# ST-LinkV2.net
KiCad netlist of a schematic drawn in Altium Designer
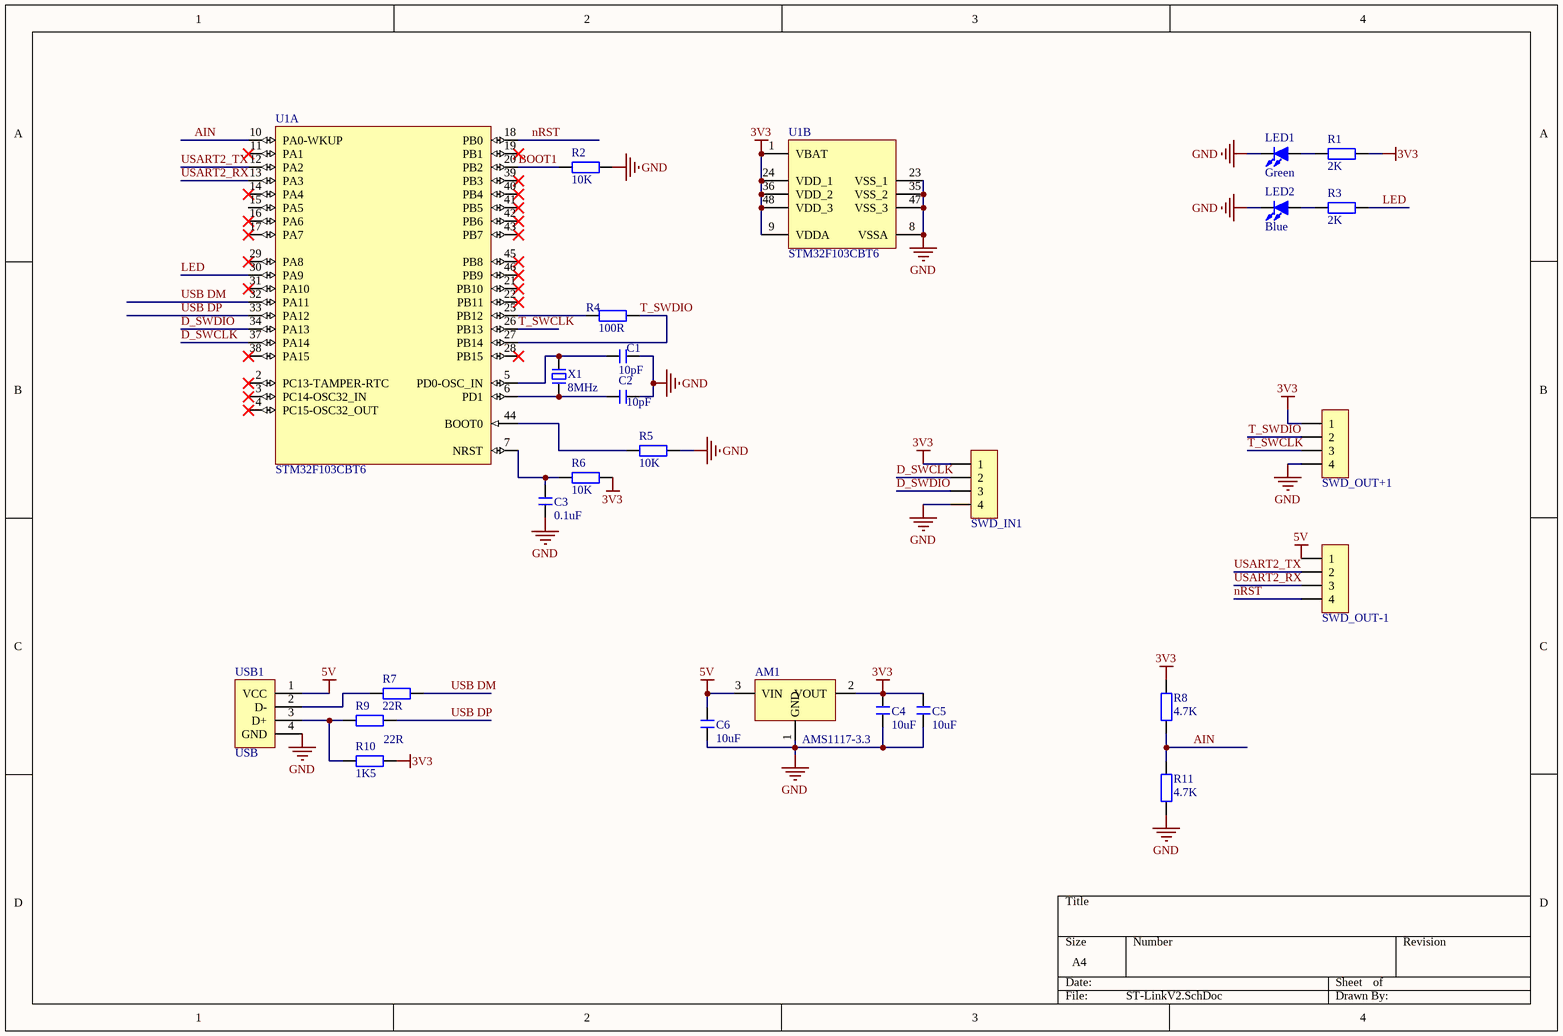
[diagram p0: ST-LinkV2.SchDoc]

(export (version "E")
  (design (tool "Eeschema 10.0.6"))
  (components
    (comp (ref "AM1")
      (value "AMS1117-3.3")
      (footprint "SOT89_M")
      (libsource (lib "ST-Link V2") (part "AMS1117-3.3"))
    )
    (comp (ref "C1")
      (value "10pF")
      (footprint "C 0402_M")
      (description "贴片电容")
      (libsource (lib "0.1 - 电阻-电容-电感") (part "C"))
    )
    (comp (ref "C2")
      (value "10pF")
      (footprint "C 0402_M")
      (description "贴片电容")
      (libsource (lib "0.1 - 电阻-电容-电感") (part "C"))
    )
    (comp (ref "C3")
      (value "0.1uF")
      (footprint "C 0402_M")
      (description "贴片电容")
      (libsource (lib "0.1 - 电阻-电容-电感") (part "C"))
    )
    (comp (ref "C4")
      (value "10uF")
      (footprint "C 0603_M")
      (description "贴片电容")
      (libsource (lib "0.1 - 电阻-电容-电感") (part "C"))
    )
    (comp (ref "C5")
      (value "10uF")
      (footprint "C 0603_M")
      (description "贴片电容")
      (libsource (lib "0.1 - 电阻-电容-电感") (part "C"))
    )
    (comp (ref "C6")
      (value "10uF")
      (footprint "C 0402_M")
      (description "贴片电容")
      (libsource (lib "0.1 - 电阻-电容-电感") (part "C"))
    )
    (comp (ref "LED1")
      (value "Green")
      (footprint "LED 0603G")
      (description "贴片LED")
      (libsource (lib "0.3 - LED发光二极管") (part "LED-SMD"))
    )
    (comp (ref "LED2")
      (value "Blue")
      (footprint "LED 0603B")
      (description "贴片LED")
      (libsource (lib "0.3 - LED发光二极管") (part "LED-SMD"))
    )
    (comp (ref "R1")
      (value "2K")
      (footprint "R 0402_L")
      (description "贴片电阻")
      (libsource (lib "0.1 - 电阻-电容-电感") (part "R"))
    )
    (comp (ref "R2")
      (value "10K")
      (footprint "R 0402_L")
      (description "贴片电阻")
      (libsource (lib "0.1 - 电阻-电容-电感") (part "R"))
    )
    (comp (ref "R3")
      (value "2K")
      (footprint "R 0402_L")
      (description "贴片电阻")
      (libsource (lib "0.1 - 电阻-电容-电感") (part "R"))
    )
    (comp (ref "R4")
      (value "100R")
      (footprint "R 0402_L")
      (description "贴片电阻")
      (libsource (lib "0.1 - 电阻-电容-电感") (part "R"))
    )
    (comp (ref "R5")
      (value "10K")
      (footprint "R 0402_L")
      (description "贴片电阻")
      (libsource (lib "0.1 - 电阻-电容-电感") (part "R"))
    )
    (comp (ref "R6")
      (value "10K")
      (footprint "R 0402_L")
      (description "贴片电阻")
      (libsource (lib "0.1 - 电阻-电容-电感") (part "R"))
    )
    (comp (ref "R7")
      (value "22R")
      (footprint "R 0402_L")
      (description "贴片电阻")
      (libsource (lib "0.1 - 电阻-电容-电感") (part "R"))
    )
    (comp (ref "R8")
      (value "4.7K")
      (footprint "R 0402_L")
      (description "贴片电阻")
      (libsource (lib "0.1 - 电阻-电容-电感") (part "R"))
    )
    (comp (ref "R9")
      (value "22R")
      (footprint "R 0402_L")
      (description "贴片电阻")
      (libsource (lib "0.1 - 电阻-电容-电感") (part "R"))
    )
    (comp (ref "R10")
      (value "1K5")
      (footprint "R 0402_L")
      (description "贴片电阻")
      (libsource (lib "0.1 - 电阻-电容-电感") (part "R"))
    )
    (comp (ref "R11")
      (value "4.7K")
      (footprint "R 0402_L")
      (description "贴片电阻")
      (libsource (lib "0.1 - 电阻-电容-电感") (part "R"))
    )
    (comp (ref "SWD_IN1")
      (value "HDR-1X4")
      (footprint "HDR2.54-LI-4P")
      (description "4P接插件")
      (libsource (lib "5.4 - 接插件-脚距2.54 (100mil) ") (part "Header 4"))
    )
    (comp (ref "SWD_OUT+1")
      (value "HDR-1X4")
      (footprint "HDR2.54-WS-4P")
      (description "4P接插件")
      (libsource (lib "5.4 - 接插件-脚距2.54 (100mil) ") (part "Header 4"))
    )
    (comp (ref "SWD_OUT-1")
      (value "HDR-1X4")
      (footprint "HDR2.54-WS-4P")
      (description "4P接插件")
      (libsource (lib "5.4 - 接插件-脚距2.54 (100mil) ") (part "Header 4"))
    )
    (comp (ref "U1")
      (value "STM32F103CBT6")
      (footprint "LQFP48_N")
      (libsource (lib "STMicroelectronics STM32 F1") (part "STM32F103CBT6"))
    )
    (comp (ref "USB1")
      (value "USB")
      (footprint "USB_A/P_A")
      (description "USB-A型公接口")
      (libsource (lib "0.8 - 以太网-音频-USB插座") (part "USB-A/P"))
    )
    (comp (ref "X1")
      (value "8MHz")
      (footprint "OSC HC-49S")
      (description "2脚无源脚晶振")
      (libsource (lib "0.5 - 保险丝-晶振-光耦") (part "XTAL-2P"))
    )
  )
  (nets
    (net (code "1") (name "/AIN") (class "Default")
      (node (ref "R11") (pin "2") (pinfunction "2_2") (pintype "passive"))
      (node (ref "R8") (pin "1") (pinfunction "1_1") (pintype "passive"))
      (node (ref "U1") (pin "10") (pinfunction "PA0-WKUP_10") (pintype "bidirectional"))
    )
    (net (code "2") (name "/BOOT1") (class "Default")
      (node (ref "R2") (pin "1") (pinfunction "1_1") (pintype "passive"))
      (node (ref "U1") (pin "20") (pinfunction "PB2_20") (pintype "bidirectional"))
    )
    (net (code "3") (name "/D_SWCLK") (class "Default")
      (node (ref "SWD_IN1") (pin "2") (pinfunction "2_2") (pintype "passive"))
      (node (ref "U1") (pin "37") (pinfunction "PA14_37") (pintype "bidirectional"))
    )
    (net (code "4") (name "/D_SWDIO") (class "Default")
      (node (ref "SWD_IN1") (pin "3") (pinfunction "3_3") (pintype "passive"))
      (node (ref "U1") (pin "34") (pinfunction "PA13_34") (pintype "bidirectional"))
    )
    (net (code "5") (name "/LED") (class "Default")
      (node (ref "R3") (pin "2") (pinfunction "2_2") (pintype "passive"))
      (node (ref "U1") (pin "30") (pinfunction "PA9_30") (pintype "bidirectional"))
    )
    (net (code "6") (name "/T_SWCLK") (class "Default")
      (node (ref "SWD_OUT+1") (pin "3") (pinfunction "3_3") (pintype "passive"))
      (node (ref "U1") (pin "26") (pinfunction "PB13_26") (pintype "bidirectional"))
    )
    (net (code "7") (name "/T_SWDIO") (class "Default")
      (node (ref "R4") (pin "2") (pinfunction "2_2") (pintype "passive"))
      (node (ref "SWD_OUT+1") (pin "2") (pinfunction "2_2") (pintype "passive"))
      (node (ref "U1") (pin "27") (pinfunction "PB14_27") (pintype "bidirectional"))
    )
    (net (code "8") (name "/USART2_RX") (class "Default")
      (node (ref "SWD_OUT-1") (pin "3") (pinfunction "3_3") (pintype "passive"))
      (node (ref "U1") (pin "13") (pinfunction "PA3_13") (pintype "bidirectional"))
    )
    (net (code "9") (name "/USART2_TX") (class "Default")
      (node (ref "SWD_OUT-1") (pin "2") (pinfunction "2_2") (pintype "passive"))
      (node (ref "U1") (pin "12") (pinfunction "PA2_12") (pintype "bidirectional"))
    )
    (net (code "10") (name "/USB DM") (class "Default")
      (node (ref "R7") (pin "2") (pinfunction "2_2") (pintype "passive"))
      (node (ref "U1") (pin "32") (pinfunction "PA11_32") (pintype "bidirectional"))
    )
    (net (code "11") (name "/USB DP") (class "Default")
      (node (ref "R9") (pin "2") (pinfunction "2_2") (pintype "passive"))
      (node (ref "U1") (pin "33") (pinfunction "PA12_33") (pintype "bidirectional"))
    )
    (net (code "12") (name "/nRST") (class "Default")
      (node (ref "SWD_OUT-1") (pin "4") (pinfunction "4_4") (pintype "passive"))
      (node (ref "U1") (pin "18") (pinfunction "PB0_18") (pintype "bidirectional"))
    )
    (net (code "13") (name "3V3") (class "Default")
      (node (ref "AM1") (pin "2") (pinfunction "VOUT_2") (pintype "passive"))
      (node (ref "C4") (pin "1") (pinfunction "1_1") (pintype "passive"))
      (node (ref "C5") (pin "1") (pinfunction "1_1") (pintype "passive"))
      (node (ref "R1") (pin "2") (pinfunction "2_2") (pintype "passive"))
      (node (ref "R10") (pin "1") (pinfunction "1_1") (pintype "passive"))
      (node (ref "R6") (pin "2") (pinfunction "2_2") (pintype "passive"))
      (node (ref "R8") (pin "2") (pinfunction "2_2") (pintype "passive"))
      (node (ref "SWD_IN1") (pin "1") (pinfunction "1_1") (pintype "passive"))
      (node (ref "SWD_OUT+1") (pin "1") (pinfunction "1_1") (pintype "passive"))
      (node (ref "U1") (pin "1") (pinfunction "VBAT_1") (pintype "power_in"))
      (node (ref "U1") (pin "24") (pinfunction "VDD_1_24") (pintype "power_in"))
      (node (ref "U1") (pin "36") (pinfunction "VDD_2_36") (pintype "power_in"))
      (node (ref "U1") (pin "48") (pinfunction "VDD_3_48") (pintype "power_in"))
      (node (ref "U1") (pin "9") (pinfunction "VDDA_9") (pintype "power_in"))
    )
    (net (code "14") (name "5V") (class "Default")
      (node (ref "AM1") (pin "3") (pinfunction "VIN_3") (pintype "passive"))
      (node (ref "C6") (pin "1") (pinfunction "1_1") (pintype "passive"))
      (node (ref "SWD_OUT-1") (pin "1") (pinfunction "1_1") (pintype "passive"))
      (node (ref "USB1") (pin "1") (pinfunction "VCC_1") (pintype "passive"))
    )
    (net (code "15") (name "GND") (class "Default")
      (node (ref "AM1") (pin "1") (pinfunction "GND_1") (pintype "passive"))
      (node (ref "C1") (pin "1") (pinfunction "1_1") (pintype "passive"))
      (node (ref "C2") (pin "1") (pinfunction "1_1") (pintype "passive"))
      (node (ref "C3") (pin "1") (pinfunction "1_1") (pintype "passive"))
      (node (ref "C4") (pin "2") (pinfunction "2_2") (pintype "passive"))
      (node (ref "C5") (pin "2") (pinfunction "2_2") (pintype "passive"))
      (node (ref "C6") (pin "2") (pinfunction "2_2") (pintype "passive"))
      (node (ref "LED1") (pin "2") (pinfunction "K_2") (pintype "passive"))
      (node (ref "LED2") (pin "2") (pinfunction "K_2") (pintype "passive"))
      (node (ref "R11") (pin "1") (pinfunction "1_1") (pintype "passive"))
      (node (ref "R2") (pin "2") (pinfunction "2_2") (pintype "passive"))
      (node (ref "R5") (pin "2") (pinfunction "2_2") (pintype "passive"))
      (node (ref "SWD_IN1") (pin "4") (pinfunction "4_4") (pintype "passive"))
      (node (ref "SWD_OUT+1") (pin "4") (pinfunction "4_4") (pintype "passive"))
      (node (ref "U1") (pin "23") (pinfunction "VSS_1_23") (pintype "power_in"))
      (node (ref "U1") (pin "35") (pinfunction "VSS_2_35") (pintype "power_in"))
      (node (ref "U1") (pin "47") (pinfunction "VSS_3_47") (pintype "power_in"))
      (node (ref "U1") (pin "8") (pinfunction "VSSA_8") (pintype "power_in"))
      (node (ref "USB1") (pin "4") (pinfunction "GND_4") (pintype "passive"))
    )
    (net (code "16") (name "Net-(LED1-A)") (class "Default")
      (node (ref "LED1") (pin "1") (pinfunction "A_1") (pintype "passive"))
      (node (ref "R1") (pin "1") (pinfunction "1_1") (pintype "passive"))
    )
    (net (code "17") (name "Net-(LED2-A)") (class "Default")
      (node (ref "LED2") (pin "1") (pinfunction "A_1") (pintype "passive"))
      (node (ref "R3") (pin "1") (pinfunction "1_1") (pintype "passive"))
    )
    (net (code "18") (name "Net-(U1A-BOOT0)") (class "Default")
      (node (ref "R5") (pin "1") (pinfunction "1_1") (pintype "passive"))
      (node (ref "U1") (pin "44") (pinfunction "BOOT0_44") (pintype "input"))
    )
    (net (code "19") (name "Net-(U1A-NRST)") (class "Default")
      (node (ref "C3") (pin "2") (pinfunction "2_2") (pintype "passive"))
      (node (ref "R6") (pin "1") (pinfunction "1_1") (pintype "passive"))
      (node (ref "U1") (pin "7") (pinfunction "NRST_7") (pintype "bidirectional"))
    )
    (net (code "20") (name "Net-(U1A-PB12)") (class "Default")
      (node (ref "R4") (pin "1") (pinfunction "1_1") (pintype "passive"))
      (node (ref "U1") (pin "25") (pinfunction "PB12_25") (pintype "bidirectional"))
    )
    (net (code "21") (name "Net-(U1A-PD0-OSC_IN)") (class "Default")
      (node (ref "C1") (pin "2") (pinfunction "2_2") (pintype "passive"))
      (node (ref "U1") (pin "5") (pinfunction "PD0-OSC_IN_5") (pintype "bidirectional"))
      (node (ref "X1") (pin "2") (pinfunction "2_2") (pintype "passive"))
    )
    (net (code "22") (name "Net-(U1A-PD1)") (class "Default")
      (node (ref "C2") (pin "2") (pinfunction "2_2") (pintype "passive"))
      (node (ref "U1") (pin "6") (pinfunction "PD1_6") (pintype "bidirectional"))
      (node (ref "X1") (pin "1") (pinfunction "1_1") (pintype "passive"))
    )
    (net (code "23") (name "Net-(USB1-D+)") (class "Default")
      (node (ref "R10") (pin "2") (pinfunction "2_2") (pintype "passive"))
      (node (ref "R9") (pin "1") (pinfunction "1_1") (pintype "passive"))
      (node (ref "USB1") (pin "3") (pinfunction "D+_3") (pintype "passive"))
    )
    (net (code "24") (name "Net-(USB1-D-)") (class "Default")
      (node (ref "R7") (pin "1") (pinfunction "1_1") (pintype "passive"))
      (node (ref "USB1") (pin "2") (pinfunction "D-_2") (pintype "passive"))
    )
    (net (code "25") (name "unconnected-(U1A-PA1-Pad11)") (class "Default")
      (node (ref "U1") (pin "11") (pinfunction "PA1_11") (pintype "bidirectional+no_connect"))
    )
    (net (code "26") (name "unconnected-(U1A-PA4-Pad14)") (class "Default")
      (node (ref "U1") (pin "14") (pinfunction "PA4_14") (pintype "bidirectional+no_connect"))
    )
    (net (code "27") (name "unconnected-(U1A-PA5-Pad15)") (class "Default")
      (node (ref "U1") (pin "15") (pinfunction "PA5_15") (pintype "bidirectional"))
    )
    (net (code "28") (name "unconnected-(U1A-PA6-Pad16)") (class "Default")
      (node (ref "U1") (pin "16") (pinfunction "PA6_16") (pintype "bidirectional+no_connect"))
    )
    (net (code "29") (name "unconnected-(U1A-PA7-Pad17)") (class "Default")
      (node (ref "U1") (pin "17") (pinfunction "PA7_17") (pintype "bidirectional+no_connect"))
    )
    (net (code "30") (name "unconnected-(U1A-PA8-Pad29)") (class "Default")
      (node (ref "U1") (pin "29") (pinfunction "PA8_29") (pintype "bidirectional+no_connect"))
    )
    (net (code "31") (name "unconnected-(U1A-PA10-Pad31)") (class "Default")
      (node (ref "U1") (pin "31") (pinfunction "PA10_31") (pintype "bidirectional+no_connect"))
    )
    (net (code "32") (name "unconnected-(U1A-PA15-Pad38)") (class "Default")
      (node (ref "U1") (pin "38") (pinfunction "PA15_38") (pintype "bidirectional+no_connect"))
    )
    (net (code "33") (name "unconnected-(U1A-PB1-Pad19)") (class "Default")
      (node (ref "U1") (pin "19") (pinfunction "PB1_19") (pintype "bidirectional+no_connect"))
    )
    (net (code "34") (name "unconnected-(U1A-PB3-Pad39)") (class "Default")
      (node (ref "U1") (pin "39") (pinfunction "PB3_39") (pintype "bidirectional+no_connect"))
    )
    (net (code "35") (name "unconnected-(U1A-PB4-Pad40)") (class "Default")
      (node (ref "U1") (pin "40") (pinfunction "PB4_40") (pintype "bidirectional+no_connect"))
    )
    (net (code "36") (name "unconnected-(U1A-PB5-Pad41)") (class "Default")
      (node (ref "U1") (pin "41") (pinfunction "PB5_41") (pintype "bidirectional+no_connect"))
    )
    (net (code "37") (name "unconnected-(U1A-PB6-Pad42)") (class "Default")
      (node (ref "U1") (pin "42") (pinfunction "PB6_42") (pintype "bidirectional+no_connect"))
    )
    (net (code "38") (name "unconnected-(U1A-PB7-Pad43)") (class "Default")
      (node (ref "U1") (pin "43") (pinfunction "PB7_43") (pintype "bidirectional+no_connect"))
    )
    (net (code "39") (name "unconnected-(U1A-PB8-Pad45)") (class "Default")
      (node (ref "U1") (pin "45") (pinfunction "PB8_45") (pintype "bidirectional+no_connect"))
    )
    (net (code "40") (name "unconnected-(U1A-PB9-Pad46)") (class "Default")
      (node (ref "U1") (pin "46") (pinfunction "PB9_46") (pintype "bidirectional+no_connect"))
    )
    (net (code "41") (name "unconnected-(U1A-PB10-Pad21)") (class "Default")
      (node (ref "U1") (pin "21") (pinfunction "PB10_21") (pintype "bidirectional+no_connect"))
    )
    (net (code "42") (name "unconnected-(U1A-PB11-Pad22)") (class "Default")
      (node (ref "U1") (pin "22") (pinfunction "PB11_22") (pintype "bidirectional+no_connect"))
    )
    (net (code "43") (name "unconnected-(U1A-PB15-Pad28)") (class "Default")
      (node (ref "U1") (pin "28") (pinfunction "PB15_28") (pintype "bidirectional+no_connect"))
    )
    (net (code "44") (name "unconnected-(U1A-PC13-TAMPER-RTC-Pad2)") (class "Default")
      (node (ref "U1") (pin "2") (pinfunction "PC13-TAMPER-RTC_2") (pintype "bidirectional+no_connect"))
    )
    (net (code "45") (name "unconnected-(U1A-PC14-OSC32_IN-Pad3)") (class "Default")
      (node (ref "U1") (pin "3") (pinfunction "PC14-OSC32_IN_3") (pintype "bidirectional+no_connect"))
    )
    (net (code "46") (name "unconnected-(U1A-PC15-OSC32_OUT-Pad4)") (class "Default")
      (node (ref "U1") (pin "4") (pinfunction "PC15-OSC32_OUT_4") (pintype "bidirectional+no_connect"))
    )
  )
)
